# Puzzle_LED_Bar-v2_0.net
KiCad netlist of a schematic drawn in EAGLE
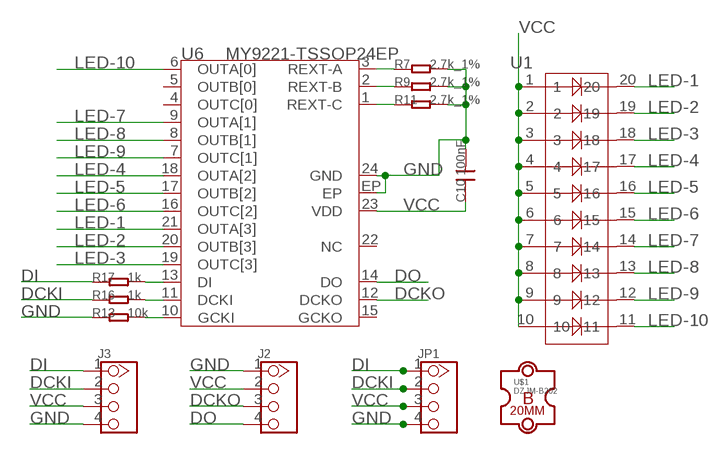
[diagram p0: schematic, sheet 1]

(export (version "E")
  (design (tool "Eeschema 10.0.6"))
  (components
    (comp (ref "C10")
      (value "100nF")
      (footprint "eagle-import:0603")
      (libsource (lib "eagle-import") (part "C-0603"))
    )
    (comp (ref "J2")
      (value "HEADER-4P-90D")
      (footprint "eagle-import:4P-2.54-90")
      (libsource (lib "eagle-import") (part "HEADER-4P-90D"))
    )
    (comp (ref "J3")
      (value "HEADER-4P'2.54-90D-FEMALE'")
      (footprint "eagle-import:4P-2.54-90D-FEMALE")
      (libsource (lib "eagle-import") (part "HEADER-4P'2.54-90D-FEMALE'"))
    )
    (comp (ref "JP1")
      (value "M0410")
      (footprint "eagle-import:JMZY-1X4")
      (libsource (lib "eagle-import") (part "M0410"))
    )
    (comp (ref "R7")
      (value "2.7k_1%")
      (footprint "eagle-import:0603")
      (libsource (lib "eagle-import") (part "R-0603"))
    )
    (comp (ref "R9")
      (value "2.7k_1%")
      (footprint "eagle-import:0603")
      (libsource (lib "eagle-import") (part "R-0603"))
    )
    (comp (ref "R11")
      (value "2.7k_1%")
      (footprint "eagle-import:0603")
      (libsource (lib "eagle-import") (part "R-0603"))
    )
    (comp (ref "R13")
      (value "10k")
      (footprint "eagle-import:0603")
      (libsource (lib "eagle-import") (part "R-0603"))
    )
    (comp (ref "R16")
      (value "1k")
      (footprint "eagle-import:0603")
      (libsource (lib "eagle-import") (part "R-0603"))
    )
    (comp (ref "R17")
      (value "1k")
      (footprint "eagle-import:0603")
      (libsource (lib "eagle-import") (part "R-0603"))
    )
    (comp (ref "U$1")
      (value "DZJM-B202")
      (footprint "eagle-import:DZJM-B20-2P")
      (libsource (lib "eagle-import") (part "DZJM-B202"))
    )
    (comp (ref "U1")
      (value "LED-20P")
      (footprint "eagle-import:20P-DIP-2.54-25.5X10.1X8.4H")
      (libsource (lib "eagle-import") (part "LED-20P"))
    )
    (comp (ref "U6")
      (value "MY9221-TSSOP24EP")
      (footprint "eagle-import:TSSOP24EP")
      (libsource (lib "eagle-import") (part "MY9221-TSSOP24EP"))
    )
  )
  (nets
    (net (code "1") (name "/DCKI") (class "Default")
      (node (ref "J3") (pin "2") (pinfunction "P$2_2") (pintype "bidirectional"))
      (node (ref "JP1") (pin "2") (pinfunction "P$2_2") (pintype "bidirectional"))
      (node (ref "R16") (pin "1") (pinfunction "1_1") (pintype "passive"))
    )
    (net (code "2") (name "/DCKO") (class "Default")
      (node (ref "J2") (pin "3") (pinfunction "P$3_3") (pintype "bidirectional"))
      (node (ref "U6") (pin "12") (pinfunction "DCKO_12") (pintype "bidirectional"))
    )
    (net (code "3") (name "/DI") (class "Default")
      (node (ref "J3") (pin "1") (pinfunction "P$1_1") (pintype "bidirectional"))
      (node (ref "JP1") (pin "1") (pinfunction "P$1_1") (pintype "bidirectional"))
      (node (ref "R17") (pin "1") (pinfunction "1_1") (pintype "passive"))
    )
    (net (code "4") (name "/DO") (class "Default")
      (node (ref "J2") (pin "4") (pinfunction "P$4_4") (pintype "bidirectional"))
      (node (ref "U6") (pin "14") (pinfunction "DO_14") (pintype "bidirectional"))
    )
    (net (code "5") (name "/GND") (class "Default")
      (node (ref "C10") (pin "2") (pinfunction "2_2") (pintype "passive"))
      (node (ref "J2") (pin "1") (pinfunction "P$1_1") (pintype "bidirectional"))
      (node (ref "J3") (pin "4") (pinfunction "P$4_4") (pintype "bidirectional"))
      (node (ref "JP1") (pin "4") (pinfunction "P$4_4") (pintype "bidirectional"))
      (node (ref "R11") (pin "2") (pinfunction "2_2") (pintype "passive"))
      (node (ref "R13") (pin "1") (pinfunction "1_1") (pintype "passive"))
      (node (ref "R7") (pin "2") (pinfunction "2_2") (pintype "passive"))
      (node (ref "R9") (pin "2") (pinfunction "2_2") (pintype "passive"))
      (node (ref "U6") (pin "24") (pinfunction "GND_24") (pintype "power_in"))
      (node (ref "U6") (pin "EP") (pinfunction "EP_EP") (pintype "bidirectional"))
    )
    (net (code "6") (name "/LED-1") (class "Default")
      (node (ref "U1") (pin "20") (pinfunction "20_20") (pintype "bidirectional"))
      (node (ref "U6") (pin "21") (pinfunction "OUTA[3]_21") (pintype "bidirectional"))
    )
    (net (code "7") (name "/LED-2") (class "Default")
      (node (ref "U1") (pin "19") (pinfunction "19_19") (pintype "bidirectional"))
      (node (ref "U6") (pin "20") (pinfunction "OUTB[3]_20") (pintype "bidirectional"))
    )
    (net (code "8") (name "/LED-3") (class "Default")
      (node (ref "U1") (pin "18") (pinfunction "18_18") (pintype "bidirectional"))
      (node (ref "U6") (pin "19") (pinfunction "OUTC[3]_19") (pintype "bidirectional"))
    )
    (net (code "9") (name "/LED-4") (class "Default")
      (node (ref "U1") (pin "17") (pinfunction "17_17") (pintype "bidirectional"))
      (node (ref "U6") (pin "18") (pinfunction "OUTA[2]_18") (pintype "bidirectional"))
    )
    (net (code "10") (name "/LED-5") (class "Default")
      (node (ref "U1") (pin "16") (pinfunction "16_16") (pintype "bidirectional"))
      (node (ref "U6") (pin "17") (pinfunction "OUTB[2]_17") (pintype "bidirectional"))
    )
    (net (code "11") (name "/LED-6") (class "Default")
      (node (ref "U1") (pin "15") (pinfunction "15_15") (pintype "bidirectional"))
      (node (ref "U6") (pin "16") (pinfunction "OUTC[2]_16") (pintype "bidirectional"))
    )
    (net (code "12") (name "/LED-7") (class "Default")
      (node (ref "U1") (pin "14") (pinfunction "14_14") (pintype "bidirectional"))
      (node (ref "U6") (pin "9") (pinfunction "OUTA[1]_9") (pintype "bidirectional"))
    )
    (net (code "13") (name "/LED-8") (class "Default")
      (node (ref "U1") (pin "13") (pinfunction "13_13") (pintype "bidirectional"))
      (node (ref "U6") (pin "8") (pinfunction "OUTB[1]_8") (pintype "bidirectional"))
    )
    (net (code "14") (name "/LED-9") (class "Default")
      (node (ref "U1") (pin "12") (pinfunction "12_12") (pintype "bidirectional"))
      (node (ref "U6") (pin "7") (pinfunction "OUTC[1]_7") (pintype "bidirectional"))
    )
    (net (code "15") (name "/LED-10") (class "Default")
      (node (ref "U1") (pin "11") (pinfunction "11_11") (pintype "bidirectional"))
      (node (ref "U6") (pin "6") (pinfunction "OUTA[0]_6") (pintype "bidirectional"))
    )
    (net (code "16") (name "/VCC") (class "Default")
      (node (ref "C10") (pin "1") (pinfunction "1_1") (pintype "passive"))
      (node (ref "J2") (pin "2") (pinfunction "P$2_2") (pintype "bidirectional"))
      (node (ref "J3") (pin "3") (pinfunction "P$3_3") (pintype "bidirectional"))
      (node (ref "JP1") (pin "3") (pinfunction "P$3_3") (pintype "bidirectional"))
      (node (ref "U1") (pin "1") (pinfunction "1_1") (pintype "bidirectional"))
      (node (ref "U1") (pin "10") (pinfunction "10_10") (pintype "bidirectional"))
      (node (ref "U1") (pin "2") (pinfunction "2_2") (pintype "bidirectional"))
      (node (ref "U1") (pin "3") (pinfunction "3_3") (pintype "bidirectional"))
      (node (ref "U1") (pin "4") (pinfunction "4_4") (pintype "bidirectional"))
      (node (ref "U1") (pin "5") (pinfunction "5_5") (pintype "bidirectional"))
      (node (ref "U1") (pin "6") (pinfunction "6_6") (pintype "bidirectional"))
      (node (ref "U1") (pin "7") (pinfunction "7_7") (pintype "bidirectional"))
      (node (ref "U1") (pin "8") (pinfunction "8_8") (pintype "bidirectional"))
      (node (ref "U1") (pin "9") (pinfunction "9_9") (pintype "bidirectional"))
      (node (ref "U6") (pin "23") (pinfunction "VDD_23") (pintype "power_in"))
    )
    (net (code "17") (name "Net-(U6-DCKI)") (class "Default")
      (node (ref "R16") (pin "2") (pinfunction "2_2") (pintype "passive"))
      (node (ref "U6") (pin "11") (pinfunction "DCKI_11") (pintype "bidirectional"))
    )
    (net (code "18") (name "Net-(U6-DI)") (class "Default")
      (node (ref "R17") (pin "2") (pinfunction "2_2") (pintype "passive"))
      (node (ref "U6") (pin "13") (pinfunction "DI_13") (pintype "bidirectional"))
    )
    (net (code "19") (name "Net-(U6-GCKI)") (class "Default")
      (node (ref "R13") (pin "2") (pinfunction "2_2") (pintype "passive"))
      (node (ref "U6") (pin "10") (pinfunction "GCKI_10") (pintype "bidirectional"))
    )
    (net (code "20") (name "Net-(U6-REXT-A)") (class "Default")
      (node (ref "R7") (pin "1") (pinfunction "1_1") (pintype "passive"))
      (node (ref "U6") (pin "3") (pinfunction "REXT-A_3") (pintype "bidirectional"))
    )
    (net (code "21") (name "Net-(U6-REXT-B)") (class "Default")
      (node (ref "R9") (pin "1") (pinfunction "1_1") (pintype "passive"))
      (node (ref "U6") (pin "2") (pinfunction "REXT-B_2") (pintype "bidirectional"))
    )
    (net (code "22") (name "Net-(U6-REXT-C)") (class "Default")
      (node (ref "R11") (pin "1") (pinfunction "1_1") (pintype "passive"))
      (node (ref "U6") (pin "1") (pinfunction "REXT-C_1") (pintype "bidirectional"))
    )
    (net (code "23") (name "unconnected-(U6-GCKO-Pad15)") (class "Default")
      (node (ref "U6") (pin "15") (pinfunction "GCKO_15") (pintype "bidirectional"))
    )
    (net (code "24") (name "unconnected-(U6-NC-Pad22)") (class "Default")
      (node (ref "U6") (pin "22") (pinfunction "NC_22") (pintype "bidirectional"))
    )
    (net (code "25") (name "unconnected-(U6-OUTB[0]-Pad5)") (class "Default")
      (node (ref "U6") (pin "5") (pinfunction "OUTB[0]_5") (pintype "bidirectional"))
    )
    (net (code "26") (name "unconnected-(U6-OUTC[0]-Pad4)") (class "Default")
      (node (ref "U6") (pin "4") (pinfunction "OUTC[0]_4") (pintype "bidirectional"))
    )
  )
)
